# X8R_analog_sensor.net
KiCad netlist of a schematic drawn in EAGLE
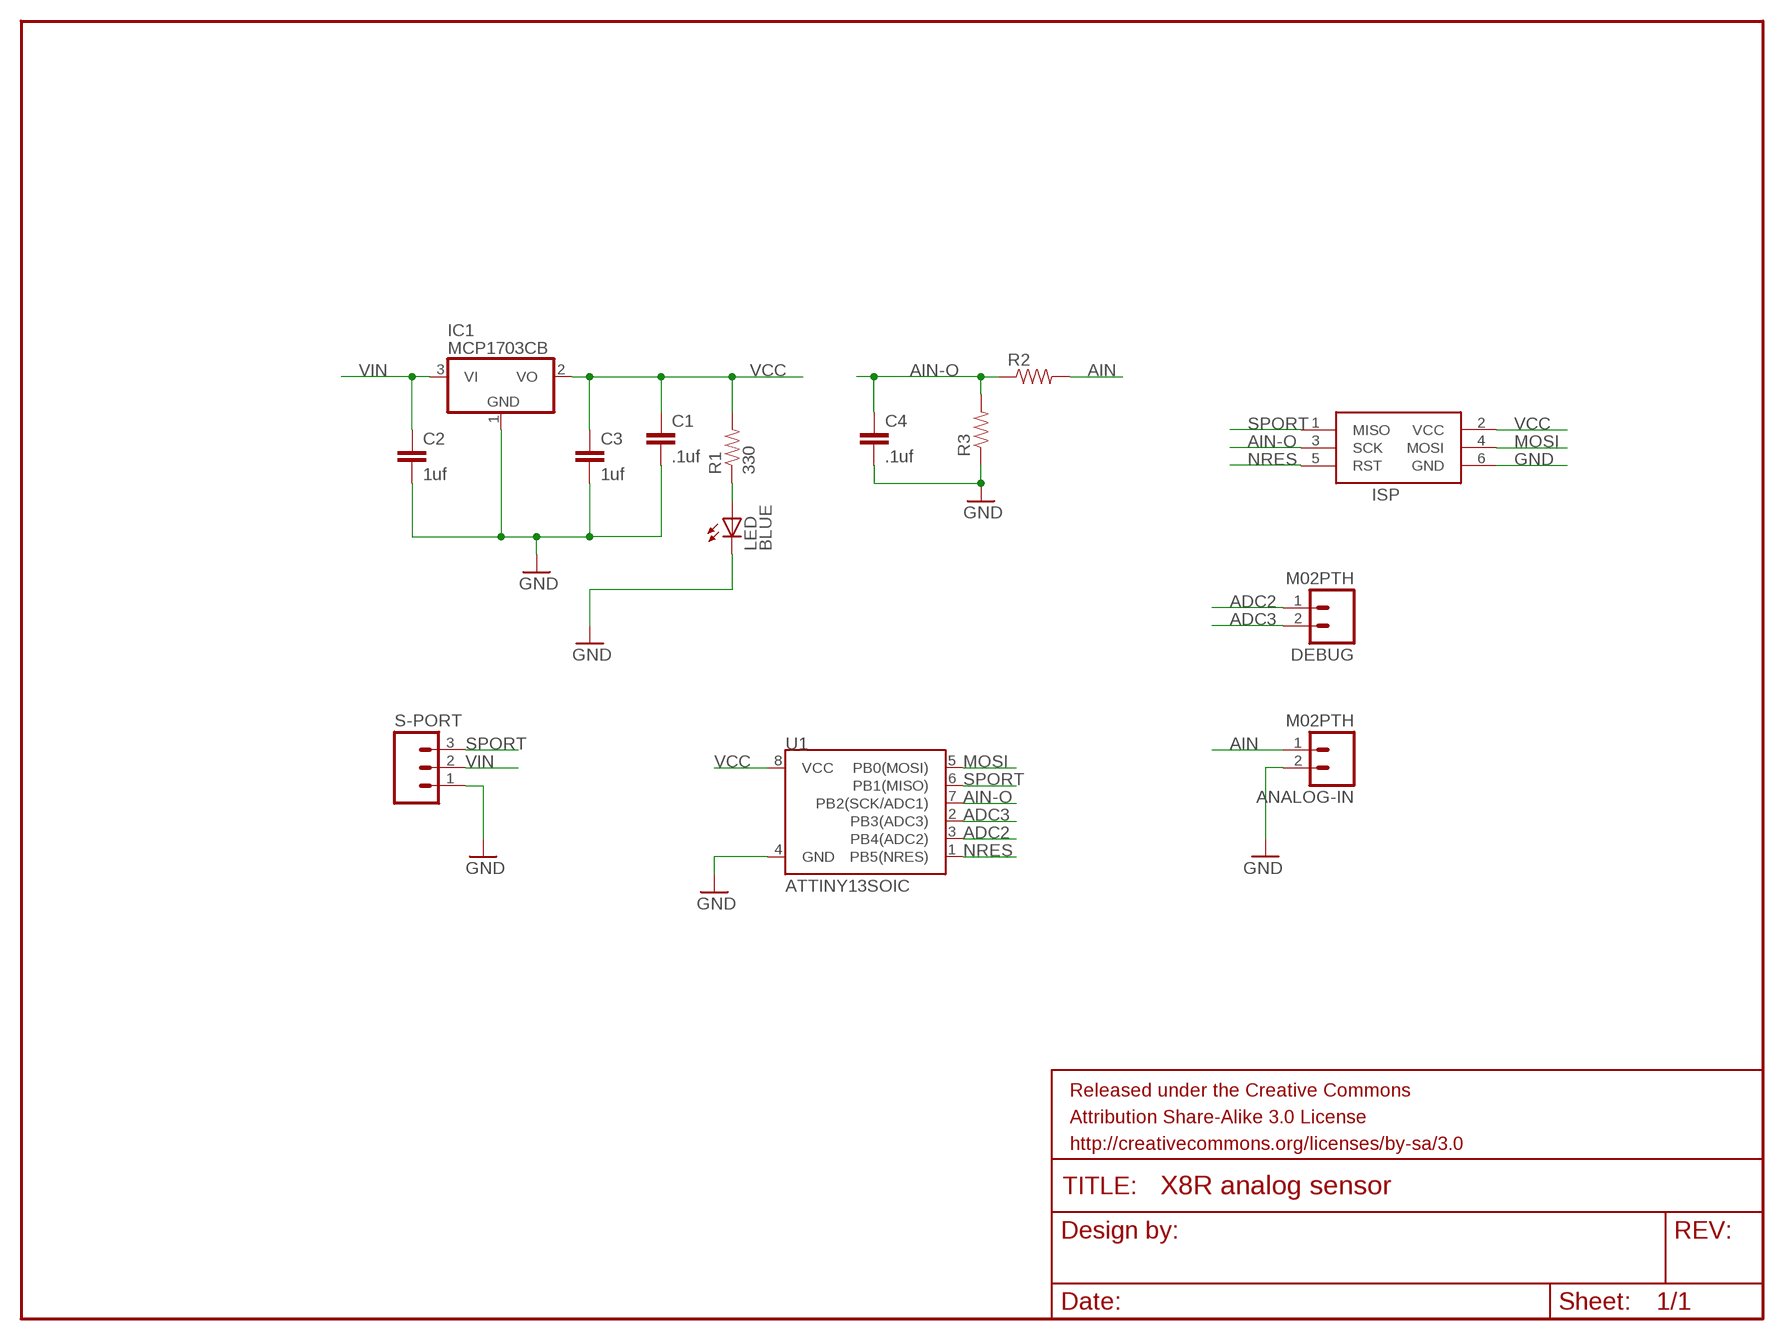
[diagram p0: schematic, sheet 1]

(export (version "E")
  (design (tool "Eeschema 10.0.6"))
  (components
    (comp (ref "ANALOG-IN")
      (value "M02PTH")
      (footprint "eagle-import:1X02")
      (libsource (lib "eagle-import") (part "M02PTH"))
    )
    (comp (ref "C1")
      (value ".1uf")
      (footprint "eagle-import:0603-CAP")
      (libsource (lib "eagle-import") (part "CAP0603-CAP"))
    )
    (comp (ref "C2")
      (value "1uf")
      (footprint "eagle-import:0603-CAP")
      (libsource (lib "eagle-import") (part "CAP0603-CAP"))
    )
    (comp (ref "C3")
      (value "1uf")
      (footprint "eagle-import:0603-CAP")
      (libsource (lib "eagle-import") (part "CAP0603-CAP"))
    )
    (comp (ref "C4")
      (value ".1uf")
      (footprint "eagle-import:0603-CAP")
      (libsource (lib "eagle-import") (part "CAP0603-CAP"))
    )
    (comp (ref "DEBUG")
      (value "M02PTH")
      (footprint "eagle-import:1X02")
      (libsource (lib "eagle-import") (part "M02PTH"))
    )
    (comp (ref "FRAME1")
      (value "FRAME-LETTER")
      (footprint "eagle-import:CREATIVE_COMMONS")
      (libsource (lib "eagle-import") (part "FRAME-LETTER"))
    )
    (comp (ref "IC1")
      (value "MCP1703CB")
      (footprint "eagle-import:SOT23")
      (libsource (lib "eagle-import") (part "MCP1703CB"))
    )
    (comp (ref "ISP")
      (value "AVRISP-6")
      (footprint "eagle-import:AVRISP")
      (libsource (lib "eagle-import") (part "AVRISP-6"))
    )
    (comp (ref "LED")
      (value "BLUE")
      (footprint "eagle-import:LED-0603")
      (libsource (lib "eagle-import") (part "LED0603"))
    )
    (comp (ref "R1")
      (value "330")
      (footprint "eagle-import:0603-RES")
      (libsource (lib "eagle-import") (part "RESISTOR0603"))
    )
    (comp (ref "R2")
      (value "RESISTORPTH-1/6W")
      (footprint "eagle-import:1_6W-RES")
      (libsource (lib "eagle-import") (part "RESISTORPTH-1/6W"))
    )
    (comp (ref "R3")
      (value "RESISTORPTH-1/6W")
      (footprint "eagle-import:1_6W-RES")
      (libsource (lib "eagle-import") (part "RESISTORPTH-1/6W"))
    )
    (comp (ref "S-PORT")
      (value "M03PTH")
      (footprint "eagle-import:1X03")
      (libsource (lib "eagle-import") (part "M03PTH"))
    )
    (comp (ref "U1")
      (value "ATTINY13SOIC")
      (footprint "eagle-import:SO08")
      (libsource (lib "eagle-import") (part "ATTINY13SOIC"))
    )
  )
  (nets
    (net (code "1") (name "/ADC2") (class "Default")
      (node (ref "DEBUG") (pin "1") (pinfunction "1_1") (pintype "passive"))
      (node (ref "U1") (pin "3") (pinfunction "PB4(ADC2)_3") (pintype "bidirectional"))
    )
    (net (code "2") (name "/ADC3") (class "Default")
      (node (ref "DEBUG") (pin "2") (pinfunction "2_2") (pintype "passive"))
      (node (ref "U1") (pin "2") (pinfunction "PB3(ADC3)_2") (pintype "bidirectional"))
    )
    (net (code "3") (name "/AIN") (class "Default")
      (node (ref "ANALOG-IN") (pin "1") (pinfunction "1_1") (pintype "passive"))
      (node (ref "R2") (pin "2") (pinfunction "2_2") (pintype "passive"))
    )
    (net (code "4") (name "/AIN-O") (class "Default")
      (node (ref "C4") (pin "1") (pinfunction "1_1") (pintype "passive"))
      (node (ref "ISP") (pin "3") (pinfunction "SCK_3") (pintype "output"))
      (node (ref "R2") (pin "1") (pinfunction "1_1") (pintype "passive"))
      (node (ref "R3") (pin "2") (pinfunction "2_2") (pintype "passive"))
      (node (ref "U1") (pin "7") (pinfunction "PB2(SCK/ADC1)_7") (pintype "bidirectional"))
    )
    (net (code "5") (name "/MOSI") (class "Default")
      (node (ref "ISP") (pin "4") (pinfunction "MOSI_4") (pintype "output"))
      (node (ref "U1") (pin "5") (pinfunction "PB0(MOSI)_5") (pintype "bidirectional"))
    )
    (net (code "6") (name "/NRES") (class "Default")
      (node (ref "ISP") (pin "5") (pinfunction "RST_5") (pintype "output"))
      (node (ref "U1") (pin "1") (pinfunction "PB5(NRES)_1") (pintype "bidirectional"))
    )
    (net (code "7") (name "/SPORT") (class "Default")
      (node (ref "ISP") (pin "1") (pinfunction "MISO_1") (pintype "input"))
      (node (ref "S-PORT") (pin "3") (pinfunction "3_3") (pintype "passive"))
      (node (ref "U1") (pin "6") (pinfunction "PB1(MISO)_6") (pintype "bidirectional"))
    )
    (net (code "8") (name "/VCC") (class "Default")
      (node (ref "C1") (pin "1") (pinfunction "1_1") (pintype "passive"))
      (node (ref "C3") (pin "1") (pinfunction "1_1") (pintype "passive"))
      (node (ref "IC1") (pin "2") (pinfunction "VO_2") (pintype "passive"))
      (node (ref "ISP") (pin "2") (pinfunction "VCC_2") (pintype "power_in"))
      (node (ref "R1") (pin "2") (pinfunction "2_2") (pintype "passive"))
      (node (ref "U1") (pin "8") (pinfunction "VCC_8") (pintype "bidirectional"))
    )
    (net (code "9") (name "/VIN") (class "Default")
      (node (ref "C2") (pin "1") (pinfunction "1_1") (pintype "passive"))
      (node (ref "IC1") (pin "3") (pinfunction "VI_3") (pintype "input"))
      (node (ref "S-PORT") (pin "2") (pinfunction "2_2") (pintype "passive"))
    )
    (net (code "10") (name "GND") (class "Default")
      (node (ref "ANALOG-IN") (pin "2") (pinfunction "2_2") (pintype "passive"))
      (node (ref "C1") (pin "2") (pinfunction "2_2") (pintype "passive"))
      (node (ref "C2") (pin "2") (pinfunction "2_2") (pintype "passive"))
      (node (ref "C3") (pin "2") (pinfunction "2_2") (pintype "passive"))
      (node (ref "C4") (pin "2") (pinfunction "2_2") (pintype "passive"))
      (node (ref "IC1") (pin "1") (pinfunction "GND_1") (pintype "passive"))
      (node (ref "ISP") (pin "6") (pinfunction "GND_6") (pintype "power_in"))
      (node (ref "LED") (pin "C") (pinfunction "C_C") (pintype "passive"))
      (node (ref "R3") (pin "1") (pinfunction "1_1") (pintype "passive"))
      (node (ref "S-PORT") (pin "1") (pinfunction "1_1") (pintype "passive"))
      (node (ref "U1") (pin "4") (pinfunction "GND_4") (pintype "bidirectional"))
    )
    (net (code "11") (name "Net-(LED-PadA)") (class "Default")
      (node (ref "LED") (pin "A") (pinfunction "A_A") (pintype "passive"))
      (node (ref "R1") (pin "1") (pinfunction "1_1") (pintype "passive"))
    )
  )
)
